# Schematics.net
KiCad netlist of a schematic drawn in Altium Designer
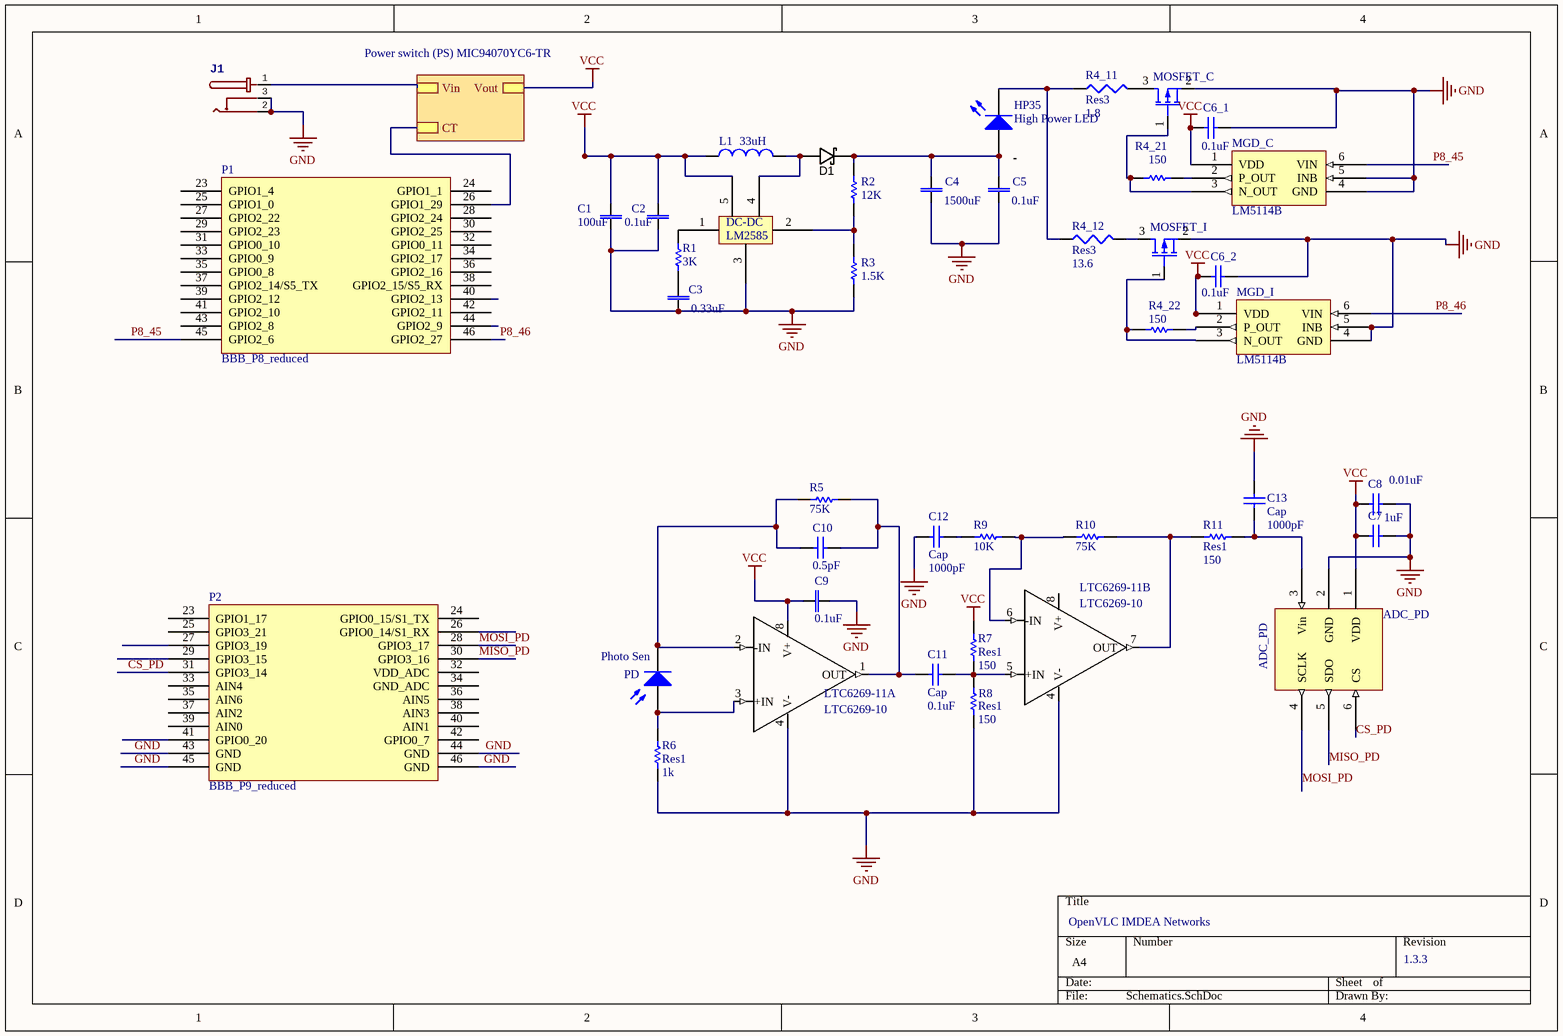
[diagram p0: Schematics.SchDoc]

(export (version "E")
  (design (tool "Eeschema 10.0.6"))
  (components
    (comp (ref "ADC_PD")
      (value "ADC_PD")
      (footprint "SOT23-6")
      (libsource (lib "BeagleBoneCape") (part "ADS7883"))
    )
    (comp (ref "C1")
      (value "100uF")
      (footprint "WCAP-ATG8 6.3x11x2.5x0.5")
      (description "Capacitor")
      (fields (field (name "Comment") "Cap") (field (name "PUBLISHER") "Altium Limited"))
      (libsource (lib "Miscellaneous Devices") (part "Cap"))
    )
    (comp (ref "C2")
      (value "0.1uF")
      (footprint "1608[0603]")
      (description "Capacitor")
      (fields (field (name "Comment") "Cap") (field (name "PUBLISHER") "Altium Limited"))
      (libsource (lib "Miscellaneous Devices") (part "Cap"))
    )
    (comp (ref "C3")
      (value "0.33uF")
      (footprint "1608[0603]")
      (description "Capacitor")
      (fields (field (name "Comment") "Cap") (field (name "PUBLISHER") "Altium Limited"))
      (libsource (lib "Miscellaneous Devices") (part "Cap"))
    )
    (comp (ref "C4")
      (value "1500uF")
      (footprint "WCAP-ATG8 10x12.5x5x0.6")
      (description "Capacitor")
      (fields (field (name "Comment") "Cap") (field (name "PUBLISHER") "Altium Limited"))
      (libsource (lib "Miscellaneous Devices") (part "Cap"))
    )
    (comp (ref "C5")
      (value "0.1uF")
      (footprint "1608[0603]")
      (description "Capacitor")
      (fields (field (name "Comment") "Cap") (field (name "PUBLISHER") "Altium Limited"))
      (libsource (lib "Miscellaneous Devices") (part "Cap"))
    )
    (comp (ref "C6_1")
      (value "0.1uF")
      (footprint "1608[0603]")
      (description "Capacitor")
      (fields (field (name "Comment") "Cap") (field (name "PUBLISHER") "Altium Limited"))
      (libsource (lib "") (part "Cap_1"))
    )
    (comp (ref "C6_2")
      (value "0.1uF")
      (footprint "1608[0603]")
      (description "Capacitor")
      (fields (field (name "Comment") "Cap") (field (name "PUBLISHER") "Altium Limited"))
      (libsource (lib "") (part "Cap_1"))
    )
    (comp (ref "C7")
      (value "1uF")
      (footprint "1608[0603]")
      (description "Capacitor")
      (fields (field (name "Comment") "Cap") (field (name "PUBLISHER") "Altium Limited"))
      (libsource (lib "") (part "Cap_1"))
    )
    (comp (ref "C8")
      (value "0.01uF")
      (footprint "1608[0603]")
      (description "Capacitor")
      (fields (field (name "Comment") "Cap") (field (name "PUBLISHER") "Altium Limited"))
      (libsource (lib "") (part "Cap_1"))
    )
    (comp (ref "C9")
      (value "0.1uF")
      (footprint "1608[0603]")
      (description "Capacitor")
      (fields (field (name "Comment") "Cap") (field (name "PUBLISHER") "Altium Limited"))
      (libsource (lib "BeagleBoneCape") (part "Cap"))
    )
    (comp (ref "C10")
      (value "0.5pF")
      (footprint "1608[0603]")
      (description "Capacitor")
      (fields (field (name "Comment") "Cap") (field (name "PUBLISHER") "Altium Limited"))
      (libsource (lib "") (part "Cap_1"))
    )
    (comp (ref "C11")
      (value "Cap")
      (footprint "1608[0603]")
      (description "Capacitor")
      (fields (field (name "ALTIUM_VALUE") "0.1uF") (field (name "PUBLISHER") "Altium Limited"))
      (libsource (lib "") (part "Cap_1"))
    )
    (comp (ref "C12")
      (value "Cap")
      (footprint "1608[0603]")
      (description "Capacitor")
      (fields (field (name "ALTIUM_VALUE") "1000pF") (field (name "PUBLISHER") "Altium Limited"))
      (libsource (lib "") (part "Cap_1"))
    )
    (comp (ref "C13")
      (value "Cap")
      (footprint "1608[0603]")
      (description "Capacitor")
      (fields (field (name "ALTIUM_VALUE") "1000pF") (field (name "PUBLISHER") "Altium Limited"))
      (libsource (lib "") (part "Cap_1"))
    )
    (comp (ref "D1")
      (value "~")
      (footprint "DO-214AC")
      (description "Diode Schottky SMD 100V 2A SMA")
      (libsource (lib "PBL - Diodes") (part "DIODE_SCHOTTKY_10MQ100NPBF"))
    )
    (comp (ref "DC-DC")
      (value "LM2585")
      (footprint "TO-263-5")
      (libsource (lib "BeagleBoneCape") (part "LM2585"))
    )
    (comp (ref "HP35")
      (value "High Power LED")
      (footprint "LEDM345X345X226:LEDM345X345X226")
      (description "Typical RED GaAs LED")
      (fields (field (name "PUBLISHER") "Altium Limited"))
      (libsource (lib "Miscellaneous Devices") (part "LED1"))
    )
    (comp (ref "J1")
      (value "2.0 mm Center Pin, 2.5 A, Right Angle, Through Hole, Tapered Pins, Dc Power Jack Connector")
      (footprint "CUI_PJ-102A")
      (fields (field (name "MF") "CUI") (field (name "MP") "PJ-102A"))
      (libsource (lib "PJ-102A") (part "PJ-102A"))
    )
    (comp (ref "L1")
      (value "33uH")
      (footprint "WCAP-ATG8:WCAP-ATG8 8x16x5x0.5")
      (description "Inductor")
      (fields (field (name "PUBLISHER") "Altium Limited"))
      (libsource (lib "Miscellaneous Devices") (part "Inductor"))
    )
    (comp (ref "LTC6269-11")
      (value "LTC6269-10")
      (footprint "SM8")
      (libsource (lib "LTC6268IS8-10_PBF") (part "LTC6269-10"))
    )
    (comp (ref "MGD_C")
      (value "LM5114B")
      (footprint "SOT23-6_N")
      (description "MOSFET Gate Driver")
      (libsource (lib "BeagleBoneCape") (part "LM5114B"))
    )
    (comp (ref "MGD_I")
      (value "LM5114B")
      (footprint "SOT23-6_N")
      (description "MOSFET Gate Driver")
      (libsource (lib "BeagleBoneCape") (part "LM5114B"))
    )
    (comp (ref "MOSFET_C")
      (value "MOSFET")
      (footprint "SOT23-3")
      (description "P-Channel MOSFET")
      (fields (field (name "PUBLISHER") "Altium Limited"))
      (libsource (lib "Miscellaneous Devices") (part "MOSFET-P"))
    )
    (comp (ref "MOSFET_I")
      (value "MOSFET")
      (footprint "SOT23-3")
      (description "P-Channel MOSFET")
      (fields (field (name "PUBLISHER") "Altium Limited"))
      (libsource (lib "Miscellaneous Devices") (part "MOSFET-P"))
    )
    (comp (ref "P1")
      (value "BBB_P8_reduced")
      (footprint "BBB_CAPE_NO_HEADER_R_24")
      (libsource (lib "BeagleBoneCape") (part "BBB_P8_reduced"))
    )
    (comp (ref "P2")
      (value "BBB_P9_reduced")
      (footprint "BBB_CAPE_NO_HEADER_R_24")
      (libsource (lib "BeagleBoneCape") (part "BBB_P9_reduced"))
    )
    (comp (ref "PD")
      (value "Photo Sen")
      (footprint "HDR1X2")
      (description "Photosensitive Diode")
      (fields (field (name "PUBLISHER") "Altium Limited"))
      (libsource (lib "Miscellaneous Devices") (part "Photo Sen"))
    )
    (comp (ref "R1")
      (value "3K")
      (footprint "1608[0603]")
      (description "Semiconductor Resistor")
      (fields (field (name "Comment") "Res Semi") (field (name "PUBLISHER") "Altium Limited"))
      (libsource (lib "Miscellaneous Devices") (part "Res Semi"))
    )
    (comp (ref "R2")
      (value "12K")
      (footprint "1608[0603]")
      (description "Resistor")
      (fields (field (name "Comment") "Res1") (field (name "PUBLISHER") "Altium Limited"))
      (libsource (lib "Miscellaneous Devices") (part "Res1"))
    )
    (comp (ref "R3")
      (value "1.5K")
      (footprint "1608[0603]")
      (description "Resistor")
      (fields (field (name "Comment") "Res1") (field (name "PUBLISHER") "Altium Limited"))
      (libsource (lib "Miscellaneous Devices") (part "Res1"))
    )
    (comp (ref "R4_11")
      (value "Res3")
      (footprint "14-1210")
      (description "Resistor")
      (fields (field (name "ALTIUM_VALUE") "1.8") (field (name "PUBLISHER") "Altium Limited"))
      (libsource (lib "Miscellaneous Devices") (part "Res3"))
    )
    (comp (ref "R4_12")
      (value "Res3")
      (footprint "14-1210")
      (description "Resistor")
      (fields (field (name "ALTIUM_VALUE") "13.6") (field (name "PUBLISHER") "Altium Limited"))
      (libsource (lib "Miscellaneous Devices") (part "Res3"))
    )
    (comp (ref "R4_21")
      (value "150")
      (footprint "1608[0603]")
      (description "Resistor")
      (fields (field (name "Comment") "Res1") (field (name "PUBLISHER") "Altium Limited"))
      (libsource (lib "Miscellaneous Devices") (part "Res1"))
    )
    (comp (ref "R4_22")
      (value "150")
      (footprint "1608[0603]")
      (description "Resistor")
      (fields (field (name "Comment") "Res1") (field (name "PUBLISHER") "Altium Limited"))
      (libsource (lib "Miscellaneous Devices") (part "Res1"))
    )
    (comp (ref "R5")
      (value "75K")
      (footprint "1608[0603]")
      (description "Resistor")
      (fields (field (name "Comment") "Res1") (field (name "PUBLISHER") "Altium Limited"))
      (libsource (lib "Miscellaneous Devices") (part "Res1"))
    )
    (comp (ref "R6")
      (value "Res1")
      (footprint "1608[0603]")
      (description "Resistor")
      (fields (field (name "ALTIUM_VALUE") "1k") (field (name "PUBLISHER") "Altium Limited"))
      (libsource (lib "Miscellaneous Devices") (part "Res1"))
    )
    (comp (ref "R7")
      (value "Res1")
      (footprint "Miscellaneous Devices:1608[0603]")
      (description "Resistor")
      (fields (field (name "ALTIUM_VALUE") "150") (field (name "PUBLISHER") "Altium Limited"))
      (libsource (lib "Miscellaneous Devices") (part "Res1"))
    )
    (comp (ref "R8")
      (value "Res1")
      (footprint "1608[0603]")
      (description "Resistor")
      (fields (field (name "ALTIUM_VALUE") "150") (field (name "PUBLISHER") "Altium Limited"))
      (libsource (lib "Miscellaneous Devices") (part "Res1"))
    )
    (comp (ref "R9")
      (value "10K")
      (footprint "1608[0603]")
      (description "Resistor")
      (fields (field (name "Comment") "Res1") (field (name "PUBLISHER") "Altium Limited"))
      (libsource (lib "Miscellaneous Devices") (part "Res1"))
    )
    (comp (ref "R10")
      (value "75K")
      (footprint "1608[0603]")
      (description "Resistor")
      (fields (field (name "Comment") "Res1") (field (name "PUBLISHER") "Altium Limited"))
      (libsource (lib "Miscellaneous Devices") (part "Res1"))
    )
    (comp (ref "R11")
      (value "Res1")
      (footprint "1608[0603]")
      (description "Resistor")
      (fields (field (name "ALTIUM_VALUE") "150") (field (name "PUBLISHER") "Altium Limited"))
      (libsource (lib "Miscellaneous Devices") (part "Res1"))
    )
  )
  (nets
    (net (code "1") (name "/CS_PD") (class "Default")
      (node (ref "ADC_PD") (pin "6") (pinfunction "CS_6") (pintype "input"))
      (node (ref "P2") (pin "31") (pinfunction "GPIO3_14_31") (pintype "passive"))
    )
    (net (code "2") (name "/CT") (class "Default")
      (node (ref "P1") (pin "26") (pinfunction "GPIO1_29_26") (pintype "passive"))
    )
    (net (code "3") (name "/MISO_PD") (class "Default")
      (node (ref "ADC_PD") (pin "5") (pinfunction "SDO_5") (pintype "output"))
      (node (ref "P2") (pin "30") (pinfunction "GPIO3_16_30") (pintype "passive"))
    )
    (net (code "4") (name "/MOSI_PD") (class "Default")
      (node (ref "ADC_PD") (pin "4") (pinfunction "SCLK_4") (pintype "output"))
      (node (ref "P2") (pin "28") (pinfunction "GPIO3_17_28") (pintype "passive"))
    )
    (net (code "5") (name "/P8_45") (class "Default")
      (node (ref "MGD_C") (pin "6") (pinfunction "VIN_6") (pintype "input"))
      (node (ref "P1") (pin "45") (pinfunction "GPIO2_6_45") (pintype "passive"))
    )
    (net (code "6") (name "/P8_46") (class "Default")
      (node (ref "MGD_I") (pin "6") (pinfunction "VIN_6") (pintype "input"))
      (node (ref "P1") (pin "46") (pinfunction "GPIO2_27_46") (pintype "passive"))
    )
    (net (code "7") (name "/Vin") (class "Default")
      (node (ref "J1") (pin "1") (pinfunction "1_1") (pintype "power_in"))
    )
    (net (code "8") (name "GND") (class "Default")
      (node (ref "ADC_PD") (pin "2") (pinfunction "GND_2") (pintype "power_in"))
      (node (ref "C1") (pin "2") (pinfunction "2_2") (pintype "passive"))
      (node (ref "C12") (pin "1") (pinfunction "1_1") (pintype "passive"))
      (node (ref "C13") (pin "2") (pinfunction "2_2") (pintype "passive"))
      (node (ref "C2") (pin "2") (pinfunction "2_2") (pintype "passive"))
      (node (ref "C3") (pin "2") (pinfunction "2_2") (pintype "passive"))
      (node (ref "C4") (pin "2") (pinfunction "2_2") (pintype "passive"))
      (node (ref "C5") (pin "2") (pinfunction "2_2") (pintype "passive"))
      (node (ref "C6_1") (pin "2") (pinfunction "2_2") (pintype "passive"))
      (node (ref "C6_2") (pin "2") (pinfunction "2_2") (pintype "passive"))
      (node (ref "C7") (pin "2") (pinfunction "2_2") (pintype "passive"))
      (node (ref "C8") (pin "2") (pinfunction "2_2") (pintype "passive"))
      (node (ref "C9") (pin "1") (pinfunction "1_1") (pintype "passive"))
      (node (ref "DC-DC") (pin "3") (pinfunction "GND_3") (pintype "passive"))
      (node (ref "J1") (pin "2") (pinfunction "2_2") (pintype "power_in"))
      (node (ref "J1") (pin "3") (pinfunction "3_3") (pintype "power_in"))
      (node (ref "LTC6269-11") (pin "4") (pinfunction "V-_4") (pintype "power_in"))
      (node (ref "MGD_C") (pin "4") (pinfunction "GND_4") (pintype "power_in"))
      (node (ref "MGD_C") (pin "5") (pinfunction "INB_5") (pintype "input"))
      (node (ref "MGD_I") (pin "4") (pinfunction "GND_4") (pintype "power_in"))
      (node (ref "MGD_I") (pin "5") (pinfunction "INB_5") (pintype "input"))
      (node (ref "MOSFET_C") (pin "2") (pinfunction "S_2") (pintype "passive"))
      (node (ref "MOSFET_I") (pin "2") (pinfunction "S_2") (pintype "passive"))
      (node (ref "P2") (pin "43") (pinfunction "GND_43") (pintype "passive"))
      (node (ref "P2") (pin "44") (pinfunction "GND_44") (pintype "passive"))
      (node (ref "P2") (pin "45") (pinfunction "GND_45") (pintype "passive"))
      (node (ref "P2") (pin "46") (pinfunction "GND_46") (pintype "passive"))
      (node (ref "R3") (pin "1") (pinfunction "1_1") (pintype "passive"))
      (node (ref "R6") (pin "1") (pinfunction "1_1") (pintype "passive"))
      (node (ref "R8") (pin "1") (pinfunction "1_1") (pintype "passive"))
    )
    (net (code "9") (name "Net-(ADC_PD-Vin)") (class "Default")
      (node (ref "ADC_PD") (pin "3") (pinfunction "Vin_3") (pintype "input"))
      (node (ref "C13") (pin "1") (pinfunction "1_1") (pintype "passive"))
      (node (ref "R11") (pin "1") (pinfunction "1_1") (pintype "passive"))
    )
    (net (code "10") (name "Net-(C3-Pad1)") (class "Default")
      (node (ref "C3") (pin "1") (pinfunction "1_1") (pintype "passive"))
      (node (ref "R1") (pin "1") (pinfunction "1_1") (pintype "passive"))
    )
    (net (code "11") (name "Net-(C12-Pad2)") (class "Default")
      (node (ref "C12") (pin "2") (pinfunction "2_2") (pintype "passive"))
      (node (ref "R9") (pin "2") (pinfunction "2_2") (pintype "passive"))
    )
    (net (code "12") (name "Net-(DC-DC-Comp)") (class "Default")
      (node (ref "DC-DC") (pin "1") (pinfunction "Comp_1") (pintype "passive"))
      (node (ref "R1") (pin "2") (pinfunction "2_2") (pintype "passive"))
    )
    (net (code "13") (name "Net-(DC-DC-Feedack)") (class "Default")
      (node (ref "DC-DC") (pin "2") (pinfunction "Feedack_2") (pintype "passive"))
      (node (ref "R2") (pin "1") (pinfunction "1_1") (pintype "passive"))
      (node (ref "R3") (pin "2") (pinfunction "2_2") (pintype "passive"))
    )
    (net (code "14") (name "Net-(DC-DC-Switch)") (class "Default")
      (node (ref "D1") (pin "A") (pinfunction "A_A") (pintype "passive"))
      (node (ref "DC-DC") (pin "4") (pinfunction "Switch_4") (pintype "passive"))
      (node (ref "L1") (pin "2") (pinfunction "2_2") (pintype "passive"))
    )
    (net (code "15") (name "Net-(HP35-A)") (class "Default")
      (node (ref "C4") (pin "1") (pinfunction "1_1") (pintype "passive"))
      (node (ref "C5") (pin "1") (pinfunction "1_1") (pintype "passive"))
      (node (ref "D1") (pin "K") (pinfunction "K_K") (pintype "passive"))
      (node (ref "HP35") (pin "1") (pinfunction "A_1") (pintype "passive"))
      (node (ref "R2") (pin "2") (pinfunction "2_2") (pintype "passive"))
    )
    (net (code "16") (name "Net-(HP35-K)") (class "Default")
      (node (ref "HP35") (pin "2") (pinfunction "K_2") (pintype "passive"))
      (node (ref "R4_11") (pin "1") (pinfunction "1_1") (pintype "passive"))
      (node (ref "R4_12") (pin "1") (pinfunction "1_1") (pintype "passive"))
    )
    (net (code "17") (name "Net-(LTC6269-11A-+IN)") (class "Default")
      (node (ref "LTC6269-11") (pin "3") (pinfunction "+IN_3") (pintype "input"))
      (node (ref "PD") (pin "1") (pinfunction "A_1") (pintype "passive"))
      (node (ref "R6") (pin "2") (pinfunction "2_2") (pintype "passive"))
    )
    (net (code "18") (name "Net-(LTC6269-11A--IN)") (class "Default")
      (node (ref "C10") (pin "1") (pinfunction "1_1") (pintype "passive"))
      (node (ref "LTC6269-11") (pin "2") (pinfunction "-IN_2") (pintype "input"))
      (node (ref "PD") (pin "2") (pinfunction "K_2") (pintype "passive"))
      (node (ref "R5") (pin "1") (pinfunction "1_1") (pintype "passive"))
    )
    (net (code "19") (name "Net-(LTC6269-11A-OUT)") (class "Default")
      (node (ref "C10") (pin "2") (pinfunction "2_2") (pintype "passive"))
      (node (ref "C11") (pin "1") (pinfunction "1_1") (pintype "passive"))
      (node (ref "LTC6269-11") (pin "1") (pinfunction "OUT_1") (pintype "output"))
      (node (ref "R5") (pin "2") (pinfunction "2_2") (pintype "passive"))
    )
    (net (code "20") (name "Net-(LTC6269-11B-+IN)") (class "Default")
      (node (ref "C11") (pin "2") (pinfunction "2_2") (pintype "passive"))
      (node (ref "LTC6269-11") (pin "5") (pinfunction "+IN_5") (pintype "input"))
      (node (ref "R7") (pin "1") (pinfunction "1_1") (pintype "passive"))
      (node (ref "R8") (pin "2") (pinfunction "2_2") (pintype "passive"))
    )
    (net (code "21") (name "Net-(LTC6269-11B--IN)") (class "Default")
      (node (ref "LTC6269-11") (pin "6") (pinfunction "-IN_6") (pintype "input"))
      (node (ref "R10") (pin "2") (pinfunction "2_2") (pintype "passive"))
      (node (ref "R9") (pin "1") (pinfunction "1_1") (pintype "passive"))
    )
    (net (code "22") (name "Net-(LTC6269-11B-OUT)") (class "Default")
      (node (ref "LTC6269-11") (pin "7") (pinfunction "OUT_7") (pintype "output"))
      (node (ref "R10") (pin "1") (pinfunction "1_1") (pintype "passive"))
      (node (ref "R11") (pin "2") (pinfunction "2_2") (pintype "passive"))
    )
    (net (code "23") (name "Net-(MGD_C-N_OUT)") (class "Default")
      (node (ref "MGD_C") (pin "3") (pinfunction "N_OUT_3") (pintype "output"))
      (node (ref "MOSFET_C") (pin "1") (pinfunction "G_1") (pintype "passive"))
      (node (ref "R4_21") (pin "1") (pinfunction "1_1") (pintype "passive"))
    )
    (net (code "24") (name "Net-(MGD_C-P_OUT)") (class "Default")
      (node (ref "MGD_C") (pin "2") (pinfunction "P_OUT_2") (pintype "output"))
      (node (ref "R4_21") (pin "2") (pinfunction "2_2") (pintype "passive"))
    )
    (net (code "25") (name "Net-(MGD_I-N_OUT)") (class "Default")
      (node (ref "MGD_I") (pin "3") (pinfunction "N_OUT_3") (pintype "output"))
      (node (ref "MOSFET_I") (pin "1") (pinfunction "G_1") (pintype "passive"))
      (node (ref "R4_22") (pin "1") (pinfunction "1_1") (pintype "passive"))
    )
    (net (code "26") (name "Net-(MGD_I-P_OUT)") (class "Default")
      (node (ref "MGD_I") (pin "2") (pinfunction "P_OUT_2") (pintype "output"))
      (node (ref "R4_22") (pin "2") (pinfunction "2_2") (pintype "passive"))
    )
    (net (code "27") (name "Net-(MOSFET_C-D)") (class "Default")
      (node (ref "MOSFET_C") (pin "3") (pinfunction "D_3") (pintype "passive"))
      (node (ref "R4_11") (pin "2") (pinfunction "2_2") (pintype "passive"))
    )
    (net (code "28") (name "Net-(MOSFET_I-D)") (class "Default")
      (node (ref "MOSFET_I") (pin "3") (pinfunction "D_3") (pintype "passive"))
      (node (ref "R4_12") (pin "2") (pinfunction "2_2") (pintype "passive"))
    )
    (net (code "29") (name "VCC") (class "Default")
      (node (ref "ADC_PD") (pin "1") (pinfunction "VDD_1") (pintype "power_in"))
      (node (ref "C1") (pin "1") (pinfunction "1_1") (pintype "passive"))
      (node (ref "C2") (pin "1") (pinfunction "1_1") (pintype "passive"))
      (node (ref "C6_1") (pin "1") (pinfunction "1_1") (pintype "passive"))
      (node (ref "C6_2") (pin "1") (pinfunction "1_1") (pintype "passive"))
      (node (ref "C7") (pin "1") (pinfunction "1_1") (pintype "passive"))
      (node (ref "C8") (pin "1") (pinfunction "1_1") (pintype "passive"))
      (node (ref "C9") (pin "2") (pinfunction "2_2") (pintype "passive"))
      (node (ref "DC-DC") (pin "5") (pinfunction "Vin_5") (pintype "passive"))
      (node (ref "L1") (pin "1") (pinfunction "1_1") (pintype "passive"))
      (node (ref "LTC6269-11") (pin "8") (pinfunction "V+_8") (pintype "power_in"))
      (node (ref "MGD_C") (pin "1") (pinfunction "VDD_1") (pintype "power_in"))
      (node (ref "MGD_I") (pin "1") (pinfunction "VDD_1") (pintype "power_in"))
      (node (ref "R7") (pin "2") (pinfunction "2_2") (pintype "passive"))
    )
    (net (code "30") (name "unconnected-(HP35-Thermal-Pad3)") (class "Default")
      (node (ref "HP35") (pin "3") (pinfunction "Thermal_3") (pintype "passive"))
    )
    (net (code "31") (name "unconnected-(LTC6269-11B-V+-Pad8)") (class "Default")
      (node (ref "LTC6269-11") (pin "8") (pinfunction "V+_8") (pintype "power_in"))
    )
    (net (code "32") (name "unconnected-(P1-GPIO0_8-Pad35)") (class "Default")
      (node (ref "P1") (pin "35") (pinfunction "GPIO0_8_35") (pintype "passive"))
    )
    (net (code "33") (name "unconnected-(P1-GPIO0_9-Pad33)") (class "Default")
      (node (ref "P1") (pin "33") (pinfunction "GPIO0_9_33") (pintype "passive"))
    )
    (net (code "34") (name "unconnected-(P1-GPIO0_10-Pad31)") (class "Default")
      (node (ref "P1") (pin "31") (pinfunction "GPIO0_10_31") (pintype "passive"))
    )
    (net (code "35") (name "unconnected-(P1-GPIO0_11-Pad32)") (class "Default")
      (node (ref "P1") (pin "32") (pinfunction "GPIO0_11_32") (pintype "passive"))
    )
    (net (code "36") (name "unconnected-(P1-GPIO1_0-Pad25)") (class "Default")
      (node (ref "P1") (pin "25") (pinfunction "GPIO1_0_25") (pintype "passive"))
    )
    (net (code "37") (name "unconnected-(P1-GPIO1_1-Pad24)") (class "Default")
      (node (ref "P1") (pin "24") (pinfunction "GPIO1_1_24") (pintype "passive"))
    )
    (net (code "38") (name "unconnected-(P1-GPIO1_4-Pad23)") (class "Default")
      (node (ref "P1") (pin "23") (pinfunction "GPIO1_4_23") (pintype "passive"))
    )
    (net (code "39") (name "unconnected-(P1-GPIO2_8-Pad43)") (class "Default")
      (node (ref "P1") (pin "43") (pinfunction "GPIO2_8_43") (pintype "passive"))
    )
    (net (code "40") (name "unconnected-(P1-GPIO2_9-Pad44)") (class "Default")
      (node (ref "P1") (pin "44") (pinfunction "GPIO2_9_44") (pintype "passive"))
    )
    (net (code "41") (name "unconnected-(P1-GPIO2_10-Pad41)") (class "Default")
      (node (ref "P1") (pin "41") (pinfunction "GPIO2_10_41") (pintype "passive"))
    )
    (net (code "42") (name "unconnected-(P1-GPIO2_11-Pad42)") (class "Default")
      (node (ref "P1") (pin "42") (pinfunction "GPIO2_11_42") (pintype "passive"))
    )
    (net (code "43") (name "unconnected-(P1-GPIO2_12-Pad39)") (class "Default")
      (node (ref "P1") (pin "39") (pinfunction "GPIO2_12_39") (pintype "passive"))
    )
    (net (code "44") (name "unconnected-(P1-GPIO2_13-Pad40)") (class "Default")
      (node (ref "P1") (pin "40") (pinfunction "GPIO2_13_40") (pintype "passive"))
    )
    (net (code "45") (name "unconnected-(P1-GPIO2_14{slash}S5_TX-Pad37)") (class "Default")
      (node (ref "P1") (pin "37") (pinfunction "GPIO2_14/S5_TX_37") (pintype "passive"))
    )
    (net (code "46") (name "unconnected-(P1-GPIO2_15{slash}S5_RX-Pad38)") (class "Default")
      (node (ref "P1") (pin "38") (pinfunction "GPIO2_15/S5_RX_38") (pintype "passive"))
    )
    (net (code "47") (name "unconnected-(P1-GPIO2_16-Pad36)") (class "Default")
      (node (ref "P1") (pin "36") (pinfunction "GPIO2_16_36") (pintype "passive"))
    )
    (net (code "48") (name "unconnected-(P1-GPIO2_17-Pad34)") (class "Default")
      (node (ref "P1") (pin "34") (pinfunction "GPIO2_17_34") (pintype "passive"))
    )
    (net (code "49") (name "unconnected-(P1-GPIO2_22-Pad27)") (class "Default")
      (node (ref "P1") (pin "27") (pinfunction "GPIO2_22_27") (pintype "passive"))
    )
    (net (code "50") (name "unconnected-(P1-GPIO2_23-Pad29)") (class "Default")
      (node (ref "P1") (pin "29") (pinfunction "GPIO2_23_29") (pintype "passive"))
    )
    (net (code "51") (name "unconnected-(P1-GPIO2_24-Pad28)") (class "Default")
      (node (ref "P1") (pin "28") (pinfunction "GPIO2_24_28") (pintype "passive"))
    )
    (net (code "52") (name "unconnected-(P1-GPIO2_25-Pad30)") (class "Default")
      (node (ref "P1") (pin "30") (pinfunction "GPIO2_25_30") (pintype "passive"))
    )
    (net (code "53") (name "unconnected-(P2-AIN0-Pad39)") (class "Default")
      (node (ref "P2") (pin "39") (pinfunction "AIN0_39") (pintype "passive"))
    )
    (net (code "54") (name "unconnected-(P2-AIN1-Pad40)") (class "Default")
      (node (ref "P2") (pin "40") (pinfunction "AIN1_40") (pintype "passive"))
    )
    (net (code "55") (name "unconnected-(P2-AIN2-Pad37)") (class "Default")
      (node (ref "P2") (pin "37") (pinfunction "AIN2_37") (pintype "passive"))
    )
    (net (code "56") (name "unconnected-(P2-AIN3-Pad38)") (class "Default")
      (node (ref "P2") (pin "38") (pinfunction "AIN3_38") (pintype "passive"))
    )
    (net (code "57") (name "unconnected-(P2-AIN4-Pad33)") (class "Default")
      (node (ref "P2") (pin "33") (pinfunction "AIN4_33") (pintype "passive"))
    )
    (net (code "58") (name "unconnected-(P2-AIN5-Pad36)") (class "Default")
      (node (ref "P2") (pin "36") (pinfunction "AIN5_36") (pintype "passive"))
    )
    (net (code "59") (name "unconnected-(P2-AIN6-Pad35)") (class "Default")
      (node (ref "P2") (pin "35") (pinfunction "AIN6_35") (pintype "passive"))
    )
    (net (code "60") (name "unconnected-(P2-GND_ADC-Pad34)") (class "Default")
      (node (ref "P2") (pin "34") (pinfunction "GND_ADC_34") (pintype "passive"))
    )
    (net (code "61") (name "unconnected-(P2-GPIO0_7-Pad42)") (class "Default")
      (node (ref "P2") (pin "42") (pinfunction "GPIO0_7_42") (pintype "passive"))
    )
    (net (code "62") (name "unconnected-(P2-GPIO0_14{slash}S1_RX-Pad26)") (class "Default")
      (node (ref "P2") (pin "26") (pinfunction "GPIO0_14/S1_RX_26") (pintype "passive"))
    )
    (net (code "63") (name "unconnected-(P2-GPIO0_15{slash}S1_TX-Pad24)") (class "Default")
      (node (ref "P2") (pin "24") (pinfunction "GPIO0_15/S1_TX_24") (pintype "passive"))
    )
    (net (code "64") (name "unconnected-(P2-GPIO0_20-Pad41)") (class "Default")
      (node (ref "P2") (pin "41") (pinfunction "GPIO0_20_41") (pintype "passive"))
    )
    (net (code "65") (name "unconnected-(P2-GPIO1_17-Pad23)") (class "Default")
      (node (ref "P2") (pin "23") (pinfunction "GPIO1_17_23") (pintype "passive"))
    )
    (net (code "66") (name "unconnected-(P2-GPIO3_15-Pad29)") (class "Default")
      (node (ref "P2") (pin "29") (pinfunction "GPIO3_15_29") (pintype "passive"))
    )
    (net (code "67") (name "unconnected-(P2-GPIO3_19-Pad27)") (class "Default")
      (node (ref "P2") (pin "27") (pinfunction "GPIO3_19_27") (pintype "passive"))
    )
    (net (code "68") (name "unconnected-(P2-GPIO3_21-Pad25)") (class "Default")
      (node (ref "P2") (pin "25") (pinfunction "GPIO3_21_25") (pintype "passive"))
    )
    (net (code "69") (name "unconnected-(P2-VDD_ADC-Pad32)") (class "Default")
      (node (ref "P2") (pin "32") (pinfunction "VDD_ADC_32") (pintype "passive"))
    )
  )
)
